# TPS613222A.net
KiCad netlist of a schematic drawn in EAGLE
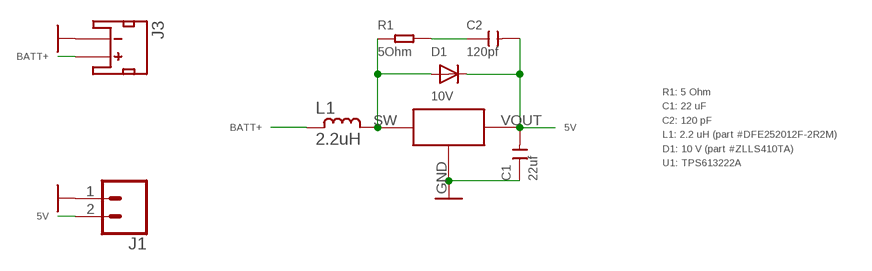
[diagram p0: schematic, sheet 1]

(export (version "E")
  (design (tool "Eeschema 10.0.6"))
  (components
    (comp (ref "C1")
      (value "22uf")
      (footprint "eagle-import:C0805")
      (fields (field (name "MPN") "CC0805MKX5R5BB226"))
      (libsource (lib "eagle-import") (part "CERAMIC-22UF-6.3V-20%-X5R(0805)"))
    )
    (comp (ref "C2")
      (value "120pf")
      (footprint "eagle-import:C0805")
      (fields (field (name "MPN") "CC0805MKX5R5BB226"))
      (libsource (lib "eagle-import") (part "CERAMIC-22UF-6.3V-20%-X5R(0805)"))
    )
    (comp (ref "D1")
      (value "10V")
      (footprint "eagle-import:SOD-323F")
      (libsource (lib "eagle-import") (part "DIODESOD-323F"))
    )
    (comp (ref "J1")
      (value "CONN_02PTH4")
      (footprint "eagle-import:1X02_XTRA_BIG")
      (libsource (lib "eagle-import") (part "CONN_02PTH4"))
    )
    (comp (ref "J3")
      (value "Batt Conn")
      (footprint "eagle-import:JST-2-SMD")
      (libsource (lib "eagle-import") (part "JST_2MM_MALE"))
    )
    (comp (ref "L1")
      (value "2.2uH")
      (footprint "eagle-import:L1008CS")
      (libsource (lib "eagle-import") (part "L-1008CS"))
    )
    (comp (ref "R1")
      (value "5Ohm")
      (footprint "eagle-import:R0805")
      (fields (field (name "MPN") "RL0805JR-070R1L"))
      (libsource (lib "eagle-import") (part "SMD-RES-0.1R-5%-1/8W(0805)"))
    )
    (comp (ref "U1")
      (value "TPS613222A")
      (footprint "eagle-import:TPS613222A")
      (libsource (lib "eagle-import") (part "TPS613222A"))
    )
  )
  (nets
    (net (code "1") (name "/5V") (class "Default")
      (node (ref "C1") (pin "2") (pinfunction "2_2") (pintype "passive"))
      (node (ref "C2") (pin "2") (pinfunction "2_2") (pintype "passive"))
      (node (ref "D1") (pin "C") (pinfunction "C_C") (pintype "passive"))
      (node (ref "J1") (pin "2") (pinfunction "2_2") (pintype "passive"))
      (node (ref "U1") (pin "VOUT") (pinfunction "VOUT_VOUT") (pintype "bidirectional"))
    )
    (net (code "2") (name "/BATT+") (class "Default")
      (node (ref "J3") (pin "2") (pinfunction "+_2") (pintype "bidirectional"))
      (node (ref "L1") (pin "1") (pinfunction "P$1_1") (pintype "passive"))
    )
    (net (code "3") (name "GND") (class "Default")
      (node (ref "C1") (pin "1") (pinfunction "1_1") (pintype "passive"))
      (node (ref "J1") (pin "1") (pinfunction "1_1") (pintype "passive"))
      (node (ref "J3") (pin "1") (pinfunction "-_1") (pintype "bidirectional"))
      (node (ref "U1") (pin "GND") (pinfunction "GND_GND") (pintype "bidirectional"))
    )
    (net (code "4") (name "Net-(C2-Pad1)") (class "Default")
      (node (ref "C2") (pin "1") (pinfunction "1_1") (pintype "passive"))
      (node (ref "R1") (pin "2") (pinfunction "2_2") (pintype "passive"))
    )
    (net (code "5") (name "Net-(L1-P$2)") (class "Default")
      (node (ref "D1") (pin "A") (pinfunction "A_A") (pintype "passive"))
      (node (ref "L1") (pin "2") (pinfunction "P$2_2") (pintype "passive"))
      (node (ref "R1") (pin "1") (pinfunction "1_1") (pintype "passive"))
      (node (ref "U1") (pin "SW") (pinfunction "SW_SW") (pintype "bidirectional"))
    )
    (net (code "6") (name "unconnected-(J3-PAD1-PadNC1)") (class "Default")
      (node (ref "J3") (pin "NC1") (pinfunction "PAD1_NC1") (pintype "bidirectional"))
    )
    (net (code "7") (name "unconnected-(J3-PAD2-PadNC2)") (class "Default")
      (node (ref "J3") (pin "NC2") (pinfunction "PAD2_NC2") (pintype "bidirectional"))
    )
  )
)
